# SparkFun_ESP32_Power_Control_Shield.net
KiCad netlist of a schematic drawn in EAGLE
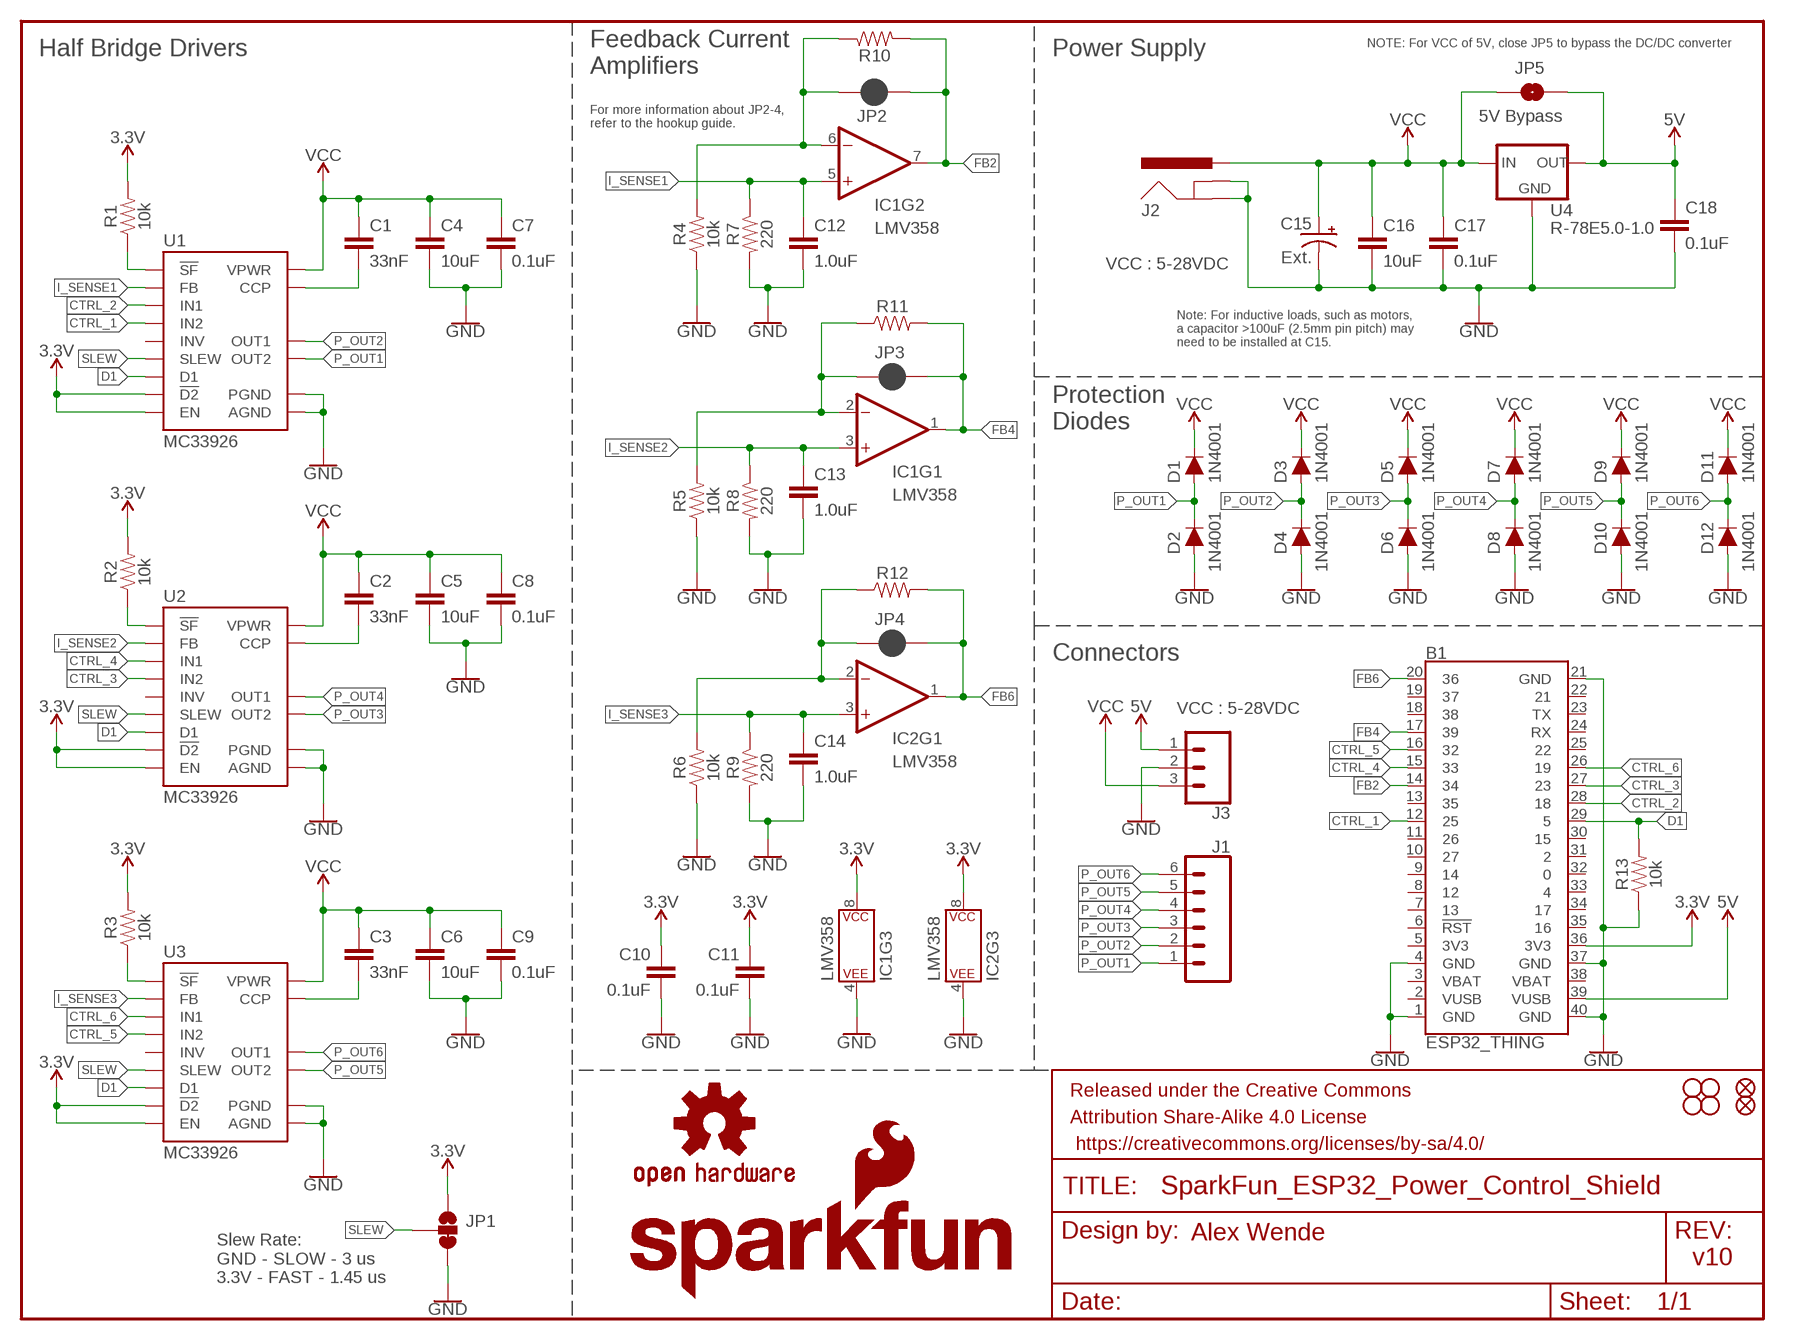
[diagram p0: schematic, sheet 1]

(export (version "E")
  (design (tool "Eeschema 10.0.6"))
  (components
    (comp (ref "B1")
      (value "ESP32_THING")
      (footprint "eagle-import:ESP32_THING")
      (libsource (lib "eagle-import") (part "ESP32_THING"))
    )
    (comp (ref "C1")
      (value "33nF")
      (footprint "eagle-import:0603")
      (libsource (lib "eagle-import") (part "33NF-0603-50V-10%"))
    )
    (comp (ref "C2")
      (value "33nF")
      (footprint "eagle-import:0603")
      (libsource (lib "eagle-import") (part "33NF-0603-50V-10%"))
    )
    (comp (ref "C3")
      (value "33nF")
      (footprint "eagle-import:0603")
      (libsource (lib "eagle-import") (part "33NF-0603-50V-10%"))
    )
    (comp (ref "C4")
      (value "10uF")
      (footprint "eagle-import:1210")
      (libsource (lib "eagle-import") (part "10UF-1210-50V-20%"))
    )
    (comp (ref "C5")
      (value "10uF")
      (footprint "eagle-import:1210")
      (libsource (lib "eagle-import") (part "10UF-1210-50V-20%"))
    )
    (comp (ref "C6")
      (value "10uF")
      (footprint "eagle-import:1210")
      (libsource (lib "eagle-import") (part "10UF-1210-50V-20%"))
    )
    (comp (ref "C7")
      (value "0.1uF")
      (footprint "eagle-import:0603")
      (libsource (lib "eagle-import") (part "0.1UF-0603-100V-10%"))
    )
    (comp (ref "C8")
      (value "0.1uF")
      (footprint "eagle-import:0603")
      (libsource (lib "eagle-import") (part "0.1UF-0603-100V-10%"))
    )
    (comp (ref "C9")
      (value "0.1uF")
      (footprint "eagle-import:0603")
      (libsource (lib "eagle-import") (part "0.1UF-0603-100V-10%"))
    )
    (comp (ref "C10")
      (value "0.1uF")
      (footprint "eagle-import:0603")
      (libsource (lib "eagle-import") (part "0.1UF-0603-100V-10%"))
    )
    (comp (ref "C11")
      (value "0.1uF")
      (footprint "eagle-import:0603")
      (libsource (lib "eagle-import") (part "0.1UF-0603-100V-10%"))
    )
    (comp (ref "C12")
      (value "1.0uF")
      (footprint "eagle-import:0603")
      (libsource (lib "eagle-import") (part "1.0UF-0603-16V-10%"))
    )
    (comp (ref "C13")
      (value "1.0uF")
      (footprint "eagle-import:0603")
      (libsource (lib "eagle-import") (part "1.0UF-0603-16V-10%"))
    )
    (comp (ref "C14")
      (value "1.0uF")
      (footprint "eagle-import:0603")
      (libsource (lib "eagle-import") (part "1.0UF-0603-16V-10%"))
    )
    (comp (ref "C15")
      (value "Ext.")
      (footprint "eagle-import:CPOL-RADIAL-2.5MM-6.5MM")
      (libsource (lib "eagle-import") (part "100UF-POLAR-RADIAL-2.5MM-25V-20%"))
    )
    (comp (ref "C16")
      (value "10uF")
      (footprint "eagle-import:1210")
      (libsource (lib "eagle-import") (part "10UF-1210-50V-20%"))
    )
    (comp (ref "C17")
      (value "0.1uF")
      (footprint "eagle-import:0603")
      (libsource (lib "eagle-import") (part "0.1UF-0603-100V-10%"))
    )
    (comp (ref "C18")
      (value "0.1uF")
      (footprint "eagle-import:0603")
      (libsource (lib "eagle-import") (part "0.1UF-0603-100V-10%"))
    )
    (comp (ref "D1")
      (value "1N4001")
      (footprint "eagle-import:DIODE-1N4001")
      (libsource (lib "eagle-import") (part "DIODE-PTH"))
    )
    (comp (ref "D2")
      (value "1N4001")
      (footprint "eagle-import:DIODE-1N4001")
      (libsource (lib "eagle-import") (part "DIODE-PTH"))
    )
    (comp (ref "D3")
      (value "1N4001")
      (footprint "eagle-import:DIODE-1N4001")
      (libsource (lib "eagle-import") (part "DIODE-PTH"))
    )
    (comp (ref "D4")
      (value "1N4001")
      (footprint "eagle-import:DIODE-1N4001")
      (libsource (lib "eagle-import") (part "DIODE-PTH"))
    )
    (comp (ref "D5")
      (value "1N4001")
      (footprint "eagle-import:DIODE-1N4001")
      (libsource (lib "eagle-import") (part "DIODE-PTH"))
    )
    (comp (ref "D6")
      (value "1N4001")
      (footprint "eagle-import:DIODE-1N4001")
      (libsource (lib "eagle-import") (part "DIODE-PTH"))
    )
    (comp (ref "D7")
      (value "1N4001")
      (footprint "eagle-import:DIODE-1N4001")
      (libsource (lib "eagle-import") (part "DIODE-PTH"))
    )
    (comp (ref "D8")
      (value "1N4001")
      (footprint "eagle-import:DIODE-1N4001")
      (libsource (lib "eagle-import") (part "DIODE-PTH"))
    )
    (comp (ref "D9")
      (value "1N4001")
      (footprint "eagle-import:DIODE-1N4001")
      (libsource (lib "eagle-import") (part "DIODE-PTH"))
    )
    (comp (ref "D10")
      (value "1N4001")
      (footprint "eagle-import:DIODE-1N4001")
      (libsource (lib "eagle-import") (part "DIODE-PTH"))
    )
    (comp (ref "D11")
      (value "1N4001")
      (footprint "eagle-import:DIODE-1N4001")
      (libsource (lib "eagle-import") (part "DIODE-PTH"))
    )
    (comp (ref "D12")
      (value "1N4001")
      (footprint "eagle-import:DIODE-1N4001")
      (libsource (lib "eagle-import") (part "DIODE-PTH"))
    )
    (comp (ref "FD1")
      (value "FIDUCIALUFIDUCIAL")
      (footprint "eagle-import:FIDUCIAL-MICRO")
      (libsource (lib "eagle-import") (part "FIDUCIALUFIDUCIAL"))
    )
    (comp (ref "FD2")
      (value "FIDUCIALUFIDUCIAL")
      (footprint "eagle-import:FIDUCIAL-MICRO")
      (libsource (lib "eagle-import") (part "FIDUCIALUFIDUCIAL"))
    )
    (comp (ref "FRAME1")
      (value "FRAME-LETTER")
      (footprint "eagle-import:CREATIVE_COMMONS")
      (libsource (lib "eagle-import") (part "FRAME-LETTER"))
    )
    (comp (ref "H1")
      (value "STAND-OFF")
      (footprint "eagle-import:STAND-OFF")
      (libsource (lib "eagle-import") (part "STAND-OFF"))
    )
    (comp (ref "H2")
      (value "STAND-OFF")
      (footprint "eagle-import:STAND-OFF")
      (libsource (lib "eagle-import") (part "STAND-OFF"))
    )
    (comp (ref "H3")
      (value "STAND-OFF")
      (footprint "eagle-import:STAND-OFF")
      (libsource (lib "eagle-import") (part "STAND-OFF"))
    )
    (comp (ref "H4")
      (value "STAND-OFF")
      (footprint "eagle-import:STAND-OFF")
      (libsource (lib "eagle-import") (part "STAND-OFF"))
    )
    (comp (ref "IC1")
      (value "LMV358")
      (footprint "eagle-import:SO08")
      (libsource (lib "eagle-import") (part "OPAMP-DUALU"))
    )
    (comp (ref "IC2")
      (value "LMV358")
      (footprint "eagle-import:SO08")
      (libsource (lib "eagle-import") (part "OPAMP-DUALU"))
    )
    (comp (ref "J1")
      (value "CONN_063.5MM-6")
      (footprint "eagle-import:SCREWTERMINAL-3.5MM-6")
      (libsource (lib "eagle-import") (part "CONN_063.5MM-6"))
    )
    (comp (ref "J2")
      (value "POWER_JACKPTH_LOCK")
      (footprint "eagle-import:POWER_JACK_PTH_LOCK")
      (libsource (lib "eagle-import") (part "POWER_JACKPTH_LOCK"))
    )
    (comp (ref "J3")
      (value "CONN_03SCREW")
      (footprint "eagle-import:SCREWTERMINAL-3.5MM-3")
      (libsource (lib "eagle-import") (part "CONN_03SCREW"))
    )
    (comp (ref "JP1")
      (value "JUMPER-SMT_3_1-NC_TRACE_SILK")
      (footprint "eagle-import:SMT-JUMPER_3_1-NC_TRACE_SILK")
      (libsource (lib "eagle-import") (part "JUMPER-SMT_3_1-NC_TRACE_SILK"))
    )
    (comp (ref "JP2")
      (value "JUMPER-SMT_2_NC_PASTE_NO-SILK")
      (footprint "eagle-import:SMT-JUMPER_2_NC_PASTE_NO-SILK")
      (libsource (lib "eagle-import") (part "JUMPER-SMT_2_NC_PASTE_NO-SILK"))
    )
    (comp (ref "JP3")
      (value "JUMPER-SMT_2_NC_PASTE_NO-SILK")
      (footprint "eagle-import:SMT-JUMPER_2_NC_PASTE_NO-SILK")
      (libsource (lib "eagle-import") (part "JUMPER-SMT_2_NC_PASTE_NO-SILK"))
    )
    (comp (ref "JP4")
      (value "JUMPER-SMT_2_NC_PASTE_NO-SILK")
      (footprint "eagle-import:SMT-JUMPER_2_NC_PASTE_NO-SILK")
      (libsource (lib "eagle-import") (part "JUMPER-SMT_2_NC_PASTE_NO-SILK"))
    )
    (comp (ref "JP5")
      (value "5V Bypass")
      (footprint "eagle-import:SMT-JUMPER_2_NO_SILK")
      (libsource (lib "eagle-import") (part "JUMPER-SMT_2_NO_SILK"))
    )
    (comp (ref "LOGO1")
      (value "SFE_LOGO_NAME_FLAME.2_INCH")
      (footprint "eagle-import:SFE_LOGO_NAME_FLAME_.2")
      (libsource (lib "eagle-import") (part "SFE_LOGO_NAME_FLAME.2_INCH"))
    )
    (comp (ref "LOGO2")
      (value "OSHW-LOGOM")
      (footprint "eagle-import:OSHW-LOGO-M")
      (libsource (lib "eagle-import") (part "OSHW-LOGOM"))
    )
    (comp (ref "R1")
      (value "10k")
      (footprint "eagle-import:0603")
      (libsource (lib "eagle-import") (part "10KOHM-0603-1/10W-1%"))
    )
    (comp (ref "R2")
      (value "10k")
      (footprint "eagle-import:0603")
      (libsource (lib "eagle-import") (part "10KOHM-0603-1/10W-1%"))
    )
    (comp (ref "R3")
      (value "10k")
      (footprint "eagle-import:0603")
      (libsource (lib "eagle-import") (part "10KOHM-0603-1/10W-1%"))
    )
    (comp (ref "R4")
      (value "10k")
      (footprint "eagle-import:0603")
      (libsource (lib "eagle-import") (part "10KOHM-0603-1/10W-1%"))
    )
    (comp (ref "R5")
      (value "10k")
      (footprint "eagle-import:0603")
      (libsource (lib "eagle-import") (part "10KOHM-0603-1/10W-1%"))
    )
    (comp (ref "R6")
      (value "10k")
      (footprint "eagle-import:0603")
      (libsource (lib "eagle-import") (part "10KOHM-0603-1/10W-1%"))
    )
    (comp (ref "R7")
      (value "220")
      (footprint "eagle-import:0603")
      (libsource (lib "eagle-import") (part "220OHM-0603-1/10W-1%"))
    )
    (comp (ref "R8")
      (value "220")
      (footprint "eagle-import:0603")
      (libsource (lib "eagle-import") (part "220OHM-0603-1/10W-1%"))
    )
    (comp (ref "R9")
      (value "220")
      (footprint "eagle-import:0603")
      (libsource (lib "eagle-import") (part "220OHM-0603-1/10W-1%"))
    )
    (comp (ref "R10")
      (value "1KOHM-HORIZ-1/4W-1%")
      (footprint "eagle-import:AXIAL-0.3")
      (libsource (lib "eagle-import") (part "1KOHM-HORIZ-1/4W-1%"))
    )
    (comp (ref "R11")
      (value "1KOHM-HORIZ-1/4W-1%")
      (footprint "eagle-import:AXIAL-0.3")
      (libsource (lib "eagle-import") (part "1KOHM-HORIZ-1/4W-1%"))
    )
    (comp (ref "R12")
      (value "1KOHM-HORIZ-1/4W-1%")
      (footprint "eagle-import:AXIAL-0.3")
      (libsource (lib "eagle-import") (part "1KOHM-HORIZ-1/4W-1%"))
    )
    (comp (ref "R13")
      (value "10k")
      (footprint "eagle-import:0603")
      (libsource (lib "eagle-import") (part "10KOHM-0603-1/10W-1%"))
    )
    (comp (ref "U1")
      (value "MC33926")
      (footprint "eagle-import:32-PQFN")
      (libsource (lib "eagle-import") (part "MC33926"))
    )
    (comp (ref "U2")
      (value "MC33926")
      (footprint "eagle-import:32-PQFN")
      (libsource (lib "eagle-import") (part "MC33926"))
    )
    (comp (ref "U3")
      (value "MC33926")
      (footprint "eagle-import:32-PQFN")
      (libsource (lib "eagle-import") (part "MC33926"))
    )
    (comp (ref "U4")
      (value "R-78E5.0-1.0")
      (footprint "eagle-import:DC-DC_CONVERTER_78XX")
      (libsource (lib "eagle-import") (part "R-78E5.0-1.0"))
    )
  )
  (nets
    (net (code "1") (name "3.3V") (class "Default")
      (node (ref "B1") (pin "36") (pinfunction "3V3_36") (pintype "bidirectional"))
      (node (ref "C10") (pin "1") (pinfunction "1_1") (pintype "passive"))
      (node (ref "C11") (pin "1") (pinfunction "1_1") (pintype "passive"))
      (node (ref "IC1") (pin "8") (pinfunction "P$V+_8") (pintype "bidirectional"))
      (node (ref "IC2") (pin "8") (pinfunction "P$V+_8") (pintype "bidirectional"))
      (node (ref "JP1") (pin "1") (pinfunction "1_1") (pintype "passive"))
      (node (ref "R1") (pin "2") (pinfunction "2_2") (pintype "passive"))
      (node (ref "R2") (pin "2") (pinfunction "2_2") (pintype "passive"))
      (node (ref "R3") (pin "2") (pinfunction "2_2") (pintype "passive"))
      (node (ref "U1") (pin "P$10") (pinfunction "EN_P$10") (pintype "bidirectional"))
      (node (ref "U1") (pin "P$16") (pinfunction "~{D2}_P$16") (pintype "bidirectional"))
      (node (ref "U2") (pin "P$10") (pinfunction "EN_P$10") (pintype "bidirectional"))
      (node (ref "U2") (pin "P$16") (pinfunction "~{D2}_P$16") (pintype "bidirectional"))
      (node (ref "U3") (pin "P$10") (pinfunction "EN_P$10") (pintype "bidirectional"))
      (node (ref "U3") (pin "P$16") (pinfunction "~{D2}_P$16") (pintype "bidirectional"))
    )
    (net (code "2") (name "5V") (class "Default")
      (node (ref "B1") (pin "39") (pinfunction "VUSB_39") (pintype "bidirectional"))
      (node (ref "C18") (pin "1") (pinfunction "1_1") (pintype "passive"))
      (node (ref "J3") (pin "1") (pinfunction "1_1") (pintype "passive"))
      (node (ref "JP5") (pin "2") (pinfunction "2_2") (pintype "passive"))
      (node (ref "U4") (pin "VOUT") (pinfunction "OUT_VOUT") (pintype "passive"))
    )
    (net (code "3") (name "CTRL_1") (class "Default")
      (node (ref "B1") (pin "12") (pinfunction "25_12") (pintype "bidirectional"))
      (node (ref "U1") (pin "P$1") (pinfunction "IN2_P$1") (pintype "bidirectional"))
    )
    (net (code "4") (name "CTRL_2") (class "Default")
      (node (ref "B1") (pin "28") (pinfunction "18_28") (pintype "bidirectional"))
      (node (ref "U1") (pin "P$2") (pinfunction "IN1_P$2") (pintype "bidirectional"))
    )
    (net (code "5") (name "CTRL_3") (class "Default")
      (node (ref "B1") (pin "27") (pinfunction "23_27") (pintype "bidirectional"))
      (node (ref "U2") (pin "P$1") (pinfunction "IN2_P$1") (pintype "bidirectional"))
    )
    (net (code "6") (name "CTRL_4") (class "Default")
      (node (ref "B1") (pin "15") (pinfunction "33_15") (pintype "bidirectional"))
      (node (ref "U2") (pin "P$2") (pinfunction "IN1_P$2") (pintype "bidirectional"))
    )
    (net (code "7") (name "CTRL_5") (class "Default")
      (node (ref "B1") (pin "16") (pinfunction "32_16") (pintype "bidirectional"))
      (node (ref "U3") (pin "P$1") (pinfunction "IN2_P$1") (pintype "bidirectional"))
    )
    (net (code "8") (name "CTRL_6") (class "Default")
      (node (ref "B1") (pin "26") (pinfunction "19_26") (pintype "bidirectional"))
      (node (ref "U3") (pin "P$2") (pinfunction "IN1_P$2") (pintype "bidirectional"))
    )
    (net (code "9") (name "D1") (class "Default")
      (node (ref "B1") (pin "29") (pinfunction "5_29") (pintype "bidirectional"))
      (node (ref "R13") (pin "2") (pinfunction "2_2") (pintype "passive"))
      (node (ref "U1") (pin "P$26") (pinfunction "D1_P$26") (pintype "bidirectional"))
      (node (ref "U2") (pin "P$26") (pinfunction "D1_P$26") (pintype "bidirectional"))
      (node (ref "U3") (pin "P$26") (pinfunction "D1_P$26") (pintype "bidirectional"))
    )
    (net (code "10") (name "FB2") (class "Default")
      (node (ref "B1") (pin "14") (pinfunction "34_14") (pintype "bidirectional"))
      (node (ref "IC1") (pin "7") (pinfunction "OUT_7") (pintype "output"))
      (node (ref "JP2") (pin "2") (pinfunction "2_2") (pintype "passive"))
      (node (ref "R10") (pin "P$2") (pinfunction "2_P$2") (pintype "passive"))
    )
    (net (code "11") (name "FB4") (class "Default")
      (node (ref "B1") (pin "17") (pinfunction "39_17") (pintype "bidirectional"))
      (node (ref "IC1") (pin "1") (pinfunction "OUT_1") (pintype "output"))
      (node (ref "JP3") (pin "2") (pinfunction "2_2") (pintype "passive"))
      (node (ref "R11") (pin "P$2") (pinfunction "2_P$2") (pintype "passive"))
    )
    (net (code "12") (name "FB6") (class "Default")
      (node (ref "B1") (pin "20") (pinfunction "36_20") (pintype "bidirectional"))
      (node (ref "IC2") (pin "1") (pinfunction "OUT_1") (pintype "output"))
      (node (ref "JP4") (pin "2") (pinfunction "2_2") (pintype "passive"))
      (node (ref "R12") (pin "P$2") (pinfunction "2_P$2") (pintype "passive"))
    )
    (net (code "13") (name "GND") (class "Default")
      (node (ref "B1") (pin "1") (pinfunction "GND_1") (pintype "bidirectional"))
      (node (ref "B1") (pin "21") (pinfunction "GND_21") (pintype "bidirectional"))
      (node (ref "B1") (pin "37") (pinfunction "GND_37") (pintype "bidirectional"))
      (node (ref "B1") (pin "4") (pinfunction "GND_4") (pintype "bidirectional"))
      (node (ref "B1") (pin "40") (pinfunction "GND_40") (pintype "bidirectional"))
      (node (ref "C10") (pin "2") (pinfunction "2_2") (pintype "passive"))
      (node (ref "C11") (pin "2") (pinfunction "2_2") (pintype "passive"))
      (node (ref "C12") (pin "2") (pinfunction "2_2") (pintype "passive"))
      (node (ref "C13") (pin "2") (pinfunction "2_2") (pintype "passive"))
      (node (ref "C14") (pin "2") (pinfunction "2_2") (pintype "passive"))
      (node (ref "C15") (pin "2") (pinfunction "-_2") (pintype "passive"))
      (node (ref "C16") (pin "2") (pinfunction "2_2") (pintype "passive"))
      (node (ref "C17") (pin "2") (pinfunction "2_2") (pintype "passive"))
      (node (ref "C18") (pin "2") (pinfunction "2_2") (pintype "passive"))
      (node (ref "C4") (pin "2") (pinfunction "2_2") (pintype "passive"))
      (node (ref "C5") (pin "2") (pinfunction "2_2") (pintype "passive"))
      (node (ref "C6") (pin "2") (pinfunction "2_2") (pintype "passive"))
      (node (ref "C7") (pin "2") (pinfunction "2_2") (pintype "passive"))
      (node (ref "C8") (pin "2") (pinfunction "2_2") (pintype "passive"))
      (node (ref "C9") (pin "2") (pinfunction "2_2") (pintype "passive"))
      (node (ref "D10") (pin "A") (pinfunction "A_A") (pintype "passive"))
      (node (ref "D12") (pin "A") (pinfunction "A_A") (pintype "passive"))
      (node (ref "D2") (pin "A") (pinfunction "A_A") (pintype "passive"))
      (node (ref "D4") (pin "A") (pinfunction "A_A") (pintype "passive"))
      (node (ref "D6") (pin "A") (pinfunction "A_A") (pintype "passive"))
      (node (ref "D8") (pin "A") (pinfunction "A_A") (pintype "passive"))
      (node (ref "IC1") (pin "4") (pinfunction "P$V-_4") (pintype "bidirectional"))
      (node (ref "IC2") (pin "4") (pinfunction "P$V-_4") (pintype "bidirectional"))
      (node (ref "J2") (pin "GND") (pinfunction "GND_GND") (pintype "bidirectional"))
      (node (ref "J2") (pin "GNDBREAK") (pinfunction "GNDBREAK_GNDBREAK") (pintype "bidirectional"))
      (node (ref "J3") (pin "2") (pinfunction "2_2") (pintype "passive"))
      (node (ref "JP1") (pin "3") (pinfunction "3_3") (pintype "passive"))
      (node (ref "R13") (pin "1") (pinfunction "1_1") (pintype "passive"))
      (node (ref "R4") (pin "1") (pinfunction "1_1") (pintype "passive"))
      (node (ref "R5") (pin "1") (pinfunction "1_1") (pintype "passive"))
      (node (ref "R6") (pin "1") (pinfunction "1_1") (pintype "passive"))
      (node (ref "R7") (pin "2") (pinfunction "2_2") (pintype "passive"))
      (node (ref "R8") (pin "2") (pinfunction "2_2") (pintype "passive"))
      (node (ref "R9") (pin "2") (pinfunction "2_2") (pintype "passive"))
      (node (ref "U1") (pin "P$18") (pinfunction "PGND_P$18") (pintype "bidirectional"))
      (node (ref "U1") (pin "P$19") (pinfunction "PGND_P$19") (pintype "bidirectional"))
      (node (ref "U1") (pin "P$20") (pinfunction "PGND_P$20") (pintype "bidirectional"))
      (node (ref "U1") (pin "P$22") (pinfunction "PGND_P$22") (pintype "bidirectional"))
      (node (ref "U1") (pin "P$23") (pinfunction "PGND_P$23") (pintype "bidirectional"))
      (node (ref "U1") (pin "P$24") (pinfunction "PGND_P$24") (pintype "bidirectional"))
      (node (ref "U1") (pin "P$33") (pinfunction "AGND_P$33") (pintype "bidirectional"))
      (node (ref "U1") (pin "P$5") (pinfunction "AGND_P$5") (pintype "bidirectional"))
      (node (ref "U2") (pin "P$18") (pinfunction "PGND_P$18") (pintype "bidirectional"))
      (node (ref "U2") (pin "P$19") (pinfunction "PGND_P$19") (pintype "bidirectional"))
      (node (ref "U2") (pin "P$20") (pinfunction "PGND_P$20") (pintype "bidirectional"))
      (node (ref "U2") (pin "P$22") (pinfunction "PGND_P$22") (pintype "bidirectional"))
      (node (ref "U2") (pin "P$23") (pinfunction "PGND_P$23") (pintype "bidirectional"))
      (node (ref "U2") (pin "P$24") (pinfunction "PGND_P$24") (pintype "bidirectional"))
      (node (ref "U2") (pin "P$33") (pinfunction "AGND_P$33") (pintype "bidirectional"))
      (node (ref "U2") (pin "P$5") (pinfunction "AGND_P$5") (pintype "bidirectional"))
      (node (ref "U3") (pin "P$18") (pinfunction "PGND_P$18") (pintype "bidirectional"))
      (node (ref "U3") (pin "P$19") (pinfunction "PGND_P$19") (pintype "bidirectional"))
      (node (ref "U3") (pin "P$20") (pinfunction "PGND_P$20") (pintype "bidirectional"))
      (node (ref "U3") (pin "P$22") (pinfunction "PGND_P$22") (pintype "bidirectional"))
      (node (ref "U3") (pin "P$23") (pinfunction "PGND_P$23") (pintype "bidirectional"))
      (node (ref "U3") (pin "P$24") (pinfunction "PGND_P$24") (pintype "bidirectional"))
      (node (ref "U3") (pin "P$33") (pinfunction "AGND_P$33") (pintype "bidirectional"))
      (node (ref "U3") (pin "P$5") (pinfunction "AGND_P$5") (pintype "bidirectional"))
      (node (ref "U4") (pin "GND") (pinfunction "GND_GND") (pintype "input"))
    )
    (net (code "14") (name "I_SENSE1") (class "Default")
      (node (ref "C12") (pin "1") (pinfunction "1_1") (pintype "passive"))
      (node (ref "IC1") (pin "5") (pinfunction "+IN_5") (pintype "input"))
      (node (ref "R7") (pin "1") (pinfunction "1_1") (pintype "passive"))
      (node (ref "U1") (pin "P$8") (pinfunction "FB_P$8") (pintype "bidirectional"))
    )
    (net (code "15") (name "I_SENSE2") (class "Default")
      (node (ref "C13") (pin "1") (pinfunction "1_1") (pintype "passive"))
      (node (ref "IC1") (pin "3") (pinfunction "+IN_3") (pintype "input"))
      (node (ref "R8") (pin "1") (pinfunction "1_1") (pintype "passive"))
      (node (ref "U2") (pin "P$8") (pinfunction "FB_P$8") (pintype "bidirectional"))
    )
    (net (code "16") (name "I_SENSE3") (class "Default")
      (node (ref "C14") (pin "1") (pinfunction "1_1") (pintype "passive"))
      (node (ref "IC2") (pin "3") (pinfunction "+IN_3") (pintype "input"))
      (node (ref "R9") (pin "1") (pinfunction "1_1") (pintype "passive"))
      (node (ref "U3") (pin "P$8") (pinfunction "FB_P$8") (pintype "bidirectional"))
    )
    (net (code "17") (name "Net-(IC1A--IN)") (class "Default")
      (node (ref "IC1") (pin "2") (pinfunction "-IN_2") (pintype "input"))
      (node (ref "JP3") (pin "1") (pinfunction "1_1") (pintype "passive"))
      (node (ref "R11") (pin "P$1") (pinfunction "1_P$1") (pintype "passive"))
      (node (ref "R5") (pin "2") (pinfunction "2_2") (pintype "passive"))
    )
    (net (code "18") (name "Net-(IC1B--IN)") (class "Default")
      (node (ref "IC1") (pin "6") (pinfunction "-IN_6") (pintype "input"))
      (node (ref "JP2") (pin "1") (pinfunction "1_1") (pintype "passive"))
      (node (ref "R10") (pin "P$1") (pinfunction "1_P$1") (pintype "passive"))
      (node (ref "R4") (pin "2") (pinfunction "2_2") (pintype "passive"))
    )
    (net (code "19") (name "Net-(IC2A--IN)") (class "Default")
      (node (ref "IC2") (pin "2") (pinfunction "-IN_2") (pintype "input"))
      (node (ref "JP4") (pin "1") (pinfunction "1_1") (pintype "passive"))
      (node (ref "R12") (pin "P$1") (pinfunction "1_P$1") (pintype "passive"))
      (node (ref "R6") (pin "2") (pinfunction "2_2") (pintype "passive"))
    )
    (net (code "20") (name "Net-(U1-CCP)") (class "Default")
      (node (ref "C1") (pin "2") (pinfunction "2_2") (pintype "passive"))
      (node (ref "U1") (pin "P$32") (pinfunction "CCP_P$32") (pintype "bidirectional"))
    )
    (net (code "21") (name "Net-(U1-~{SF})") (class "Default")
      (node (ref "R1") (pin "1") (pinfunction "1_1") (pintype "passive"))
      (node (ref "U1") (pin "P$21") (pinfunction "~{SF}_P$21") (pintype "bidirectional"))
    )
    (net (code "22") (name "Net-(U2-CCP)") (class "Default")
      (node (ref "C2") (pin "2") (pinfunction "2_2") (pintype "passive"))
      (node (ref "U2") (pin "P$32") (pinfunction "CCP_P$32") (pintype "bidirectional"))
    )
    (net (code "23") (name "Net-(U2-~{SF})") (class "Default")
      (node (ref "R2") (pin "1") (pinfunction "1_1") (pintype "passive"))
      (node (ref "U2") (pin "P$21") (pinfunction "~{SF}_P$21") (pintype "bidirectional"))
    )
    (net (code "24") (name "Net-(U3-CCP)") (class "Default")
      (node (ref "C3") (pin "2") (pinfunction "2_2") (pintype "passive"))
      (node (ref "U3") (pin "P$32") (pinfunction "CCP_P$32") (pintype "bidirectional"))
    )
    (net (code "25") (name "Net-(U3-~{SF})") (class "Default")
      (node (ref "R3") (pin "1") (pinfunction "1_1") (pintype "passive"))
      (node (ref "U3") (pin "P$21") (pinfunction "~{SF}_P$21") (pintype "bidirectional"))
    )
    (net (code "26") (name "P_OUT1") (class "Default")
      (node (ref "D1") (pin "A") (pinfunction "A_A") (pintype "passive"))
      (node (ref "D2") (pin "C") (pinfunction "C_C") (pintype "passive"))
      (node (ref "J1") (pin "1") (pinfunction "1_1") (pintype "passive"))
      (node (ref "U1") (pin "P$27") (pinfunction "OUT2_P$27") (pintype "bidirectional"))
      (node (ref "U1") (pin "P$28") (pinfunction "OUT2_P$28") (pintype "bidirectional"))
      (node (ref "U1") (pin "P$29") (pinfunction "OUT2_P$29") (pintype "bidirectional"))
      (node (ref "U1") (pin "P$30") (pinfunction "OUT2_P$30") (pintype "bidirectional"))
    )
    (net (code "27") (name "P_OUT2") (class "Default")
      (node (ref "D3") (pin "A") (pinfunction "A_A") (pintype "passive"))
      (node (ref "D4") (pin "C") (pinfunction "C_C") (pintype "passive"))
      (node (ref "J1") (pin "2") (pinfunction "2_2") (pintype "passive"))
      (node (ref "U1") (pin "P$12") (pinfunction "OUT1_P$12") (pintype "bidirectional"))
      (node (ref "U1") (pin "P$13") (pinfunction "OUT1_P$13") (pintype "bidirectional"))
      (node (ref "U1") (pin "P$14") (pinfunction "OUT1_P$14") (pintype "bidirectional"))
      (node (ref "U1") (pin "P$15") (pinfunction "OUT1_P$15") (pintype "bidirectional"))
    )
    (net (code "28") (name "P_OUT3") (class "Default")
      (node (ref "D5") (pin "A") (pinfunction "A_A") (pintype "passive"))
      (node (ref "D6") (pin "C") (pinfunction "C_C") (pintype "passive"))
      (node (ref "J1") (pin "3") (pinfunction "3_3") (pintype "passive"))
      (node (ref "U2") (pin "P$27") (pinfunction "OUT2_P$27") (pintype "bidirectional"))
      (node (ref "U2") (pin "P$28") (pinfunction "OUT2_P$28") (pintype "bidirectional"))
      (node (ref "U2") (pin "P$29") (pinfunction "OUT2_P$29") (pintype "bidirectional"))
      (node (ref "U2") (pin "P$30") (pinfunction "OUT2_P$30") (pintype "bidirectional"))
    )
    (net (code "29") (name "P_OUT4") (class "Default")
      (node (ref "D7") (pin "A") (pinfunction "A_A") (pintype "passive"))
      (node (ref "D8") (pin "C") (pinfunction "C_C") (pintype "passive"))
      (node (ref "J1") (pin "4") (pinfunction "4_4") (pintype "passive"))
      (node (ref "U2") (pin "P$12") (pinfunction "OUT1_P$12") (pintype "bidirectional"))
      (node (ref "U2") (pin "P$13") (pinfunction "OUT1_P$13") (pintype "bidirectional"))
      (node (ref "U2") (pin "P$14") (pinfunction "OUT1_P$14") (pintype "bidirectional"))
      (node (ref "U2") (pin "P$15") (pinfunction "OUT1_P$15") (pintype "bidirectional"))
    )
    (net (code "30") (name "P_OUT5") (class "Default")
      (node (ref "D10") (pin "C") (pinfunction "C_C") (pintype "passive"))
      (node (ref "D9") (pin "A") (pinfunction "A_A") (pintype "passive"))
      (node (ref "J1") (pin "5") (pinfunction "5_5") (pintype "passive"))
      (node (ref "U3") (pin "P$27") (pinfunction "OUT2_P$27") (pintype "bidirectional"))
      (node (ref "U3") (pin "P$28") (pinfunction "OUT2_P$28") (pintype "bidirectional"))
      (node (ref "U3") (pin "P$29") (pinfunction "OUT2_P$29") (pintype "bidirectional"))
      (node (ref "U3") (pin "P$30") (pinfunction "OUT2_P$30") (pintype "bidirectional"))
    )
    (net (code "31") (name "P_OUT6") (class "Default")
      (node (ref "D11") (pin "A") (pinfunction "A_A") (pintype "passive"))
      (node (ref "D12") (pin "C") (pinfunction "C_C") (pintype "passive"))
      (node (ref "J1") (pin "6") (pinfunction "6_6") (pintype "passive"))
      (node (ref "U3") (pin "P$12") (pinfunction "OUT1_P$12") (pintype "bidirectional"))
      (node (ref "U3") (pin "P$13") (pinfunction "OUT1_P$13") (pintype "bidirectional"))
      (node (ref "U3") (pin "P$14") (pinfunction "OUT1_P$14") (pintype "bidirectional"))
      (node (ref "U3") (pin "P$15") (pinfunction "OUT1_P$15") (pintype "bidirectional"))
    )
    (net (code "32") (name "SLEW") (class "Default")
      (node (ref "JP1") (pin "2") (pinfunction "2_2") (pintype "passive"))
      (node (ref "U1") (pin "P$3") (pinfunction "SLEW_P$3") (pintype "bidirectional"))
      (node (ref "U2") (pin "P$3") (pinfunction "SLEW_P$3") (pintype "bidirectional"))
      (node (ref "U3") (pin "P$3") (pinfunction "SLEW_P$3") (pintype "bidirectional"))
    )
    (net (code "33") (name "VCC") (class "Default")
      (node (ref "C1") (pin "1") (pinfunction "1_1") (pintype "passive"))
      (node (ref "C15") (pin "1") (pinfunction "+_1") (pintype "passive"))
      (node (ref "C16") (pin "1") (pinfunction "1_1") (pintype "passive"))
      (node (ref "C17") (pin "1") (pinfunction "1_1") (pintype "passive"))
      (node (ref "C2") (pin "1") (pinfunction "1_1") (pintype "passive"))
      (node (ref "C3") (pin "1") (pinfunction "1_1") (pintype "passive"))
      (node (ref "C4") (pin "1") (pinfunction "1_1") (pintype "passive"))
      (node (ref "C5") (pin "1") (pinfunction "1_1") (pintype "passive"))
      (node (ref "C6") (pin "1") (pinfunction "1_1") (pintype "passive"))
      (node (ref "C7") (pin "1") (pinfunction "1_1") (pintype "passive"))
      (node (ref "C8") (pin "1") (pinfunction "1_1") (pintype "passive"))
      (node (ref "C9") (pin "1") (pinfunction "1_1") (pintype "passive"))
      (node (ref "D1") (pin "C") (pinfunction "C_C") (pintype "passive"))
      (node (ref "D11") (pin "C") (pinfunction "C_C") (pintype "passive"))
      (node (ref "D3") (pin "C") (pinfunction "C_C") (pintype "passive"))
      (node (ref "D5") (pin "C") (pinfunction "C_C") (pintype "passive"))
      (node (ref "D7") (pin "C") (pinfunction "C_C") (pintype "passive"))
      (node (ref "D9") (pin "C") (pinfunction "C_C") (pintype "passive"))
      (node (ref "J2") (pin "PWR") (pinfunction "PWR_PWR") (pintype "bidirectional"))
      (node (ref "J3") (pin "3") (pinfunction "3_3") (pintype "passive"))
      (node (ref "JP5") (pin "1") (pinfunction "1_1") (pintype "passive"))
      (node (ref "U1") (pin "P$11") (pinfunction "VPWR_P$11") (pintype "bidirectional"))
      (node (ref "U1") (pin "P$31") (pinfunction "VPWR_P$31") (pintype "bidirectional"))
      (node (ref "U1") (pin "P$4") (pinfunction "VPWR_P$4") (pintype "bidirectional"))
      (node (ref "U1") (pin "P$6") (pinfunction "VPWR_P$6") (pintype "bidirectional"))
      (node (ref "U2") (pin "P$11") (pinfunction "VPWR_P$11") (pintype "bidirectional"))
      (node (ref "U2") (pin "P$31") (pinfunction "VPWR_P$31") (pintype "bidirectional"))
      (node (ref "U2") (pin "P$4") (pinfunction "VPWR_P$4") (pintype "bidirectional"))
      (node (ref "U2") (pin "P$6") (pinfunction "VPWR_P$6") (pintype "bidirectional"))
      (node (ref "U3") (pin "P$11") (pinfunction "VPWR_P$11") (pintype "bidirectional"))
      (node (ref "U3") (pin "P$31") (pinfunction "VPWR_P$31") (pintype "bidirectional"))
      (node (ref "U3") (pin "P$4") (pinfunction "VPWR_P$4") (pintype "bidirectional"))
      (node (ref "U3") (pin "P$6") (pinfunction "VPWR_P$6") (pintype "bidirectional"))
      (node (ref "U4") (pin "VIN") (pinfunction "IN_VIN") (pintype "input"))
    )
    (net (code "34") (name "unconnected-(B1-0-Pad32)") (class "Default")
      (node (ref "B1") (pin "32") (pinfunction "0_32") (pintype "bidirectional"))
    )
    (net (code "35") (name "unconnected-(B1-2-Pad31)") (class "Default")
      (node (ref "B1") (pin "31") (pinfunction "2_31") (pintype "bidirectional"))
    )
    (net (code "36") (name "unconnected-(B1-3V3-Pad5)") (class "Default")
      (node (ref "B1") (pin "5") (pinfunction "3V3_5") (pintype "bidirectional"))
    )
    (net (code "37") (name "unconnected-(B1-4-Pad33)") (class "Default")
      (node (ref "B1") (pin "33") (pinfunction "4_33") (pintype "bidirectional"))
    )
    (net (code "38") (name "unconnected-(B1-12-Pad8)") (class "Default")
      (node (ref "B1") (pin "8") (pinfunction "12_8") (pintype "bidirectional"))
    )
    (net (code "39") (name "unconnected-(B1-13-Pad7)") (class "Default")
      (node (ref "B1") (pin "7") (pinfunction "13_7") (pintype "bidirectional"))
    )
    (net (code "40") (name "unconnected-(B1-14-Pad9)") (class "Default")
      (node (ref "B1") (pin "9") (pinfunction "14_9") (pintype "bidirectional"))
    )
    (net (code "41") (name "unconnected-(B1-15-Pad30)") (class "Default")
      (node (ref "B1") (pin "30") (pinfunction "15_30") (pintype "bidirectional"))
    )
    (net (code "42") (name "unconnected-(B1-16-Pad35)") (class "Default")
      (node (ref "B1") (pin "35") (pinfunction "16_35") (pintype "bidirectional"))
    )
    (net (code "43") (name "unconnected-(B1-17-Pad34)") (class "Default")
      (node (ref "B1") (pin "34") (pinfunction "17_34") (pintype "bidirectional"))
    )
    (net (code "44") (name "unconnected-(B1-21-Pad22)") (class "Default")
      (node (ref "B1") (pin "22") (pinfunction "21_22") (pintype "bidirectional"))
    )
    (net (code "45") (name "unconnected-(B1-22-Pad25)") (class "Default")
      (node (ref "B1") (pin "25") (pinfunction "22_25") (pintype "bidirectional"))
    )
    (net (code "46") (name "unconnected-(B1-26-Pad11)") (class "Default")
      (node (ref "B1") (pin "11") (pinfunction "26_11") (pintype "bidirectional"))
    )
    (net (code "47") (name "unconnected-(B1-27-Pad10)") (class "Default")
      (node (ref "B1") (pin "10") (pinfunction "27_10") (pintype "bidirectional"))
    )
    (net (code "48") (name "unconnected-(B1-35-Pad13)") (class "Default")
      (node (ref "B1") (pin "13") (pinfunction "35_13") (pintype "bidirectional"))
    )
    (net (code "49") (name "unconnected-(B1-37-Pad19)") (class "Default")
      (node (ref "B1") (pin "19") (pinfunction "37_19") (pintype "bidirectional"))
    )
    (net (code "50") (name "unconnected-(B1-38-Pad18)") (class "Default")
      (node (ref "B1") (pin "18") (pinfunction "38_18") (pintype "bidirectional"))
    )
    (net (code "51") (name "unconnected-(B1-RX-Pad24)") (class "Default")
      (node (ref "B1") (pin "24") (pinfunction "RX_24") (pintype "bidirectional"))
    )
    (net (code "52") (name "unconnected-(B1-TX-Pad23)") (class "Default")
      (node (ref "B1") (pin "23") (pinfunction "TX_23") (pintype "bidirectional"))
    )
    (net (code "53") (name "unconnected-(B1-VBAT-Pad3)") (class "Default")
      (node (ref "B1") (pin "3") (pinfunction "VBAT_3") (pintype "bidirectional"))
    )
    (net (code "54") (name "unconnected-(B1-VBAT-Pad38)") (class "Default")
      (node (ref "B1") (pin "38") (pinfunction "VBAT_38") (pintype "bidirectional"))
    )
    (net (code "55") (name "unconnected-(B1-VUSB-Pad2)") (class "Default")
      (node (ref "B1") (pin "2") (pinfunction "VUSB_2") (pintype "bidirectional"))
    )
    (net (code "56") (name "unconnected-(B1-~{RST}-Pad6)") (class "Default")
      (node (ref "B1") (pin "6") (pinfunction "~{RST}_6") (pintype "bidirectional"))
    )
    (net (code "57") (name "unconnected-(U1-INV-PadP$7)") (class "Default")
      (node (ref "U1") (pin "P$7") (pinfunction "INV_P$7") (pintype "bidirectional"))
    )
    (net (code "58") (name "unconnected-(U2-INV-PadP$7)") (class "Default")
      (node (ref "U2") (pin "P$7") (pinfunction "INV_P$7") (pintype "bidirectional"))
    )
    (net (code "59") (name "unconnected-(U3-INV-PadP$7)") (class "Default")
      (node (ref "U3") (pin "P$7") (pinfunction "INV_P$7") (pintype "bidirectional"))
    )
  )
)
